# ch455_module.net
KiCad netlist of a schematic drawn in EasyEDA Pro
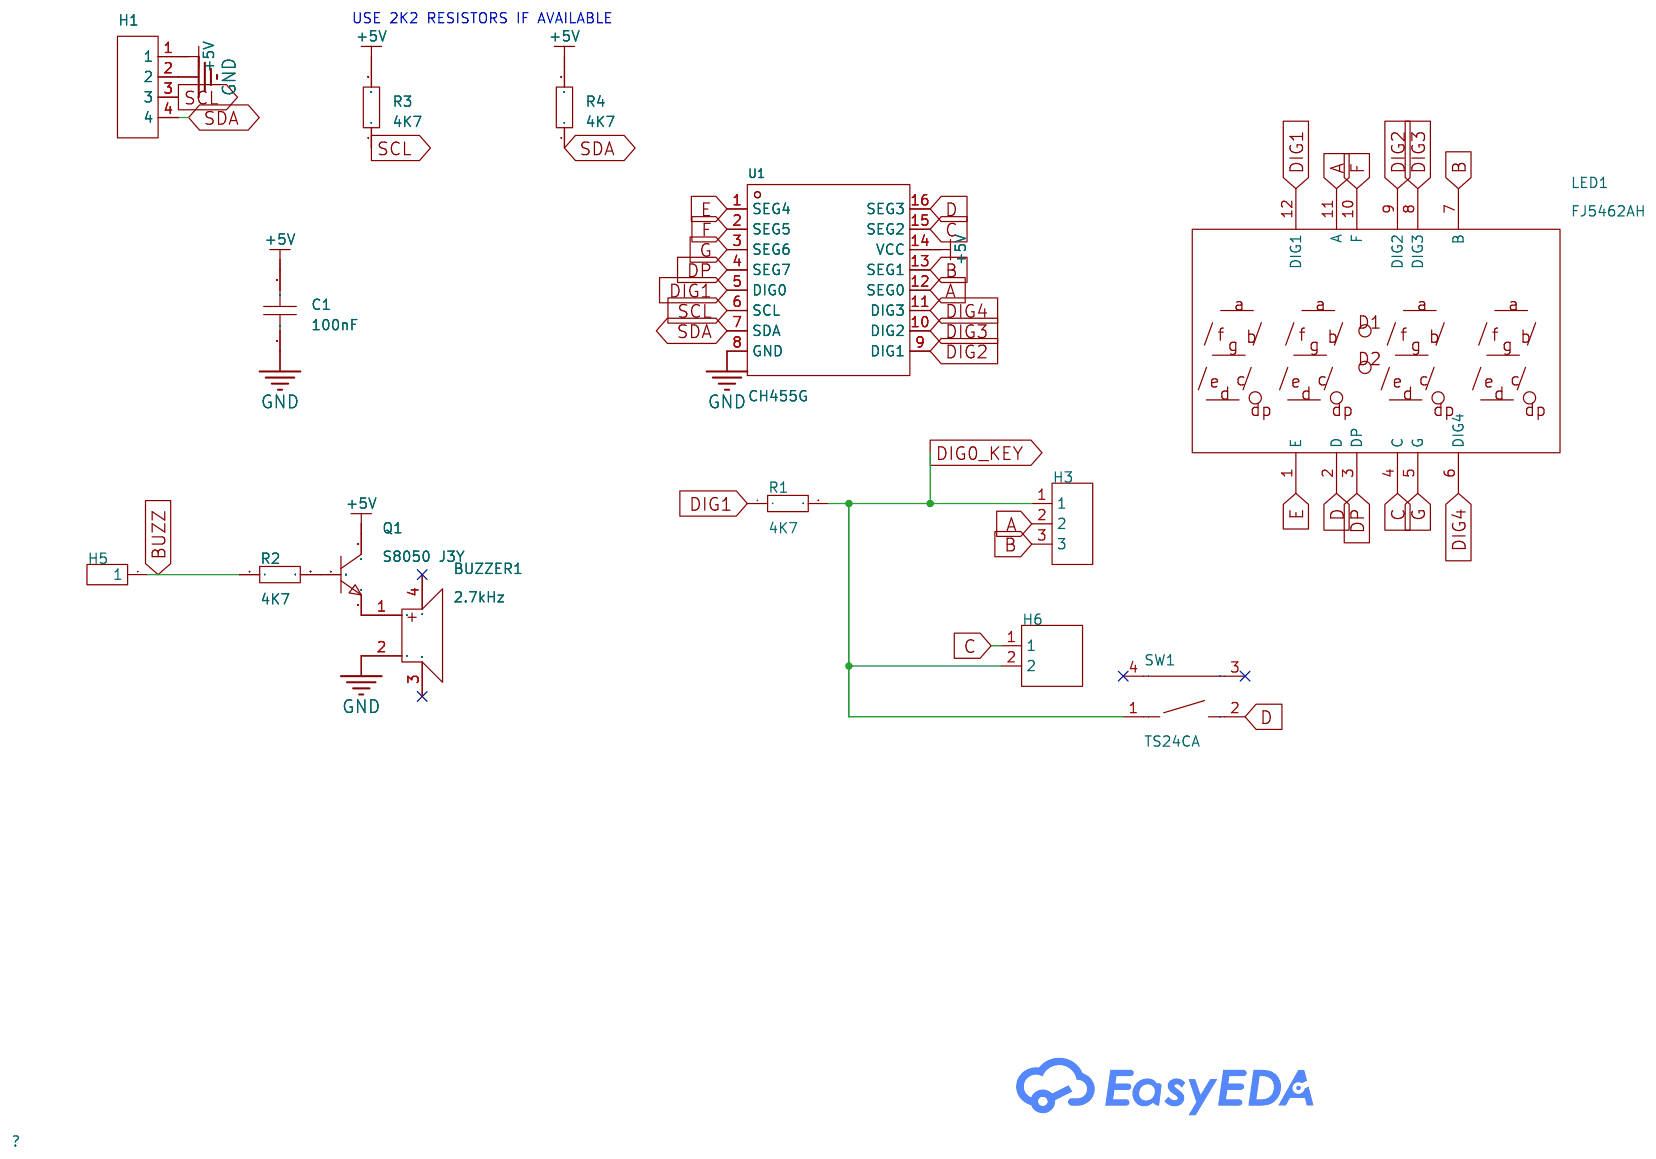
[diagram p0: schematic sheet]

(export (version "E")
  (design (tool "Eeschema 10.0.6"))
  (components
    (comp (ref "BUZZER1")
      (value "2.7kHz")
      (footprint "easyedapro:BUZ-SMD_4P-L8.5-W8.5_FUET-8530-05")
      (fields (field (name "Manufacturer Part") "SMD8530-32Ω") (field (name "Manufacturer") "XHXDZ(兴华鑫)"))
      (libsource (lib "easyedapro") (part "SMD8530-32Ω"))
    )
    (comp (ref "C1")
      (value "100nF")
      (footprint "easyedapro:C0603")
      (libsource (lib "easyedapro") (part "CAP"))
    )
    (comp (ref "H1")
      (value "~")
      (footprint "easyedapro:HDR-TH_4P-P2.54-V-M")
      (libsource (lib "easyedapro") (part "PZ254V-11-04P"))
    )
    (comp (ref "H3")
      (value "~")
      (footprint "easyedapro:HDR-TH_3P-P2.54-V-M")
      (libsource (lib "easyedapro") (part "PZ254V-11-03P_C2937625"))
    )
    (comp (ref "H5")
      (value "~")
      (footprint "easyedapro:HDR-TH_1P-V-M_XKB_X4611WV-01I-C28D40")
      (libsource (lib "easyedapro") (part "HDR_1x1"))
    )
    (comp (ref "H6")
      (value "~")
      (footprint "easyedapro:HDR-TH_2P-P2.54-V-M-1")
      (libsource (lib "easyedapro") (part "210S-1*2P L=11.6MMGold-plated black"))
    )
    (comp (ref "LED1")
      (value "FJ5462AH")
      (footprint "easyedapro:LED-SEG-TH_12P-L50.3-W19.0-P2.54-S15.24-BL")
      (fields (field (name "Manufacturer") "志浩"))
      (libsource (lib "easyedapro") (part "FJ5462AH"))
    )
    (comp (ref "Q1")
      (value "S8050 J3Y")
      (footprint "easyedapro:SOT-23-3_L2.9-W1.3-P0.95-LS2.4-BR")
      (fields (field (name "Manufacturer") "TDSEMIC(拓电半导体)"))
      (libsource (lib "easyedapro") (part "S8050 J3Y_C42441446"))
    )
    (comp (ref "R1") (value "4K7") (footprint "easyedapro:R0603") (libsource (lib "easyedapro") (part "Res")))
    (comp (ref "R2") (value "4K7") (footprint "easyedapro:R0603") (libsource (lib "easyedapro") (part "Res")))
    (comp (ref "R3") (value "4K7") (footprint "easyedapro:R0603") (libsource (lib "easyedapro") (part "Res")))
    (comp (ref "R4") (value "4K7") (footprint "easyedapro:R0603") (libsource (lib "easyedapro") (part "Res")))
    (comp (ref "SW1")
      (value "TS24CA")
      (footprint "easyedapro:SW-SMD_2P-TS24CA")
      (fields (field (name "Manufacturer") "SHOU HAN(首韩)"))
      (libsource (lib "easyedapro") (part "TS24CA"))
    )
    (comp (ref "U1")
      (value "CH455G")
      (footprint "easyedapro:SOP-16_L10.0-W3.9-P1.27-LS6.0-BL")
      (fields (field (name "Manufacturer") "WCH(南京沁恒)"))
      (libsource (lib "easyedapro") (part "CH455G"))
    )
  )
  (nets
    (net (code "1") (name "+5V") (class "Default")
      (node (ref "C1") (pin "1") (pinfunction "1_1") (pintype "input"))
      (node (ref "H1") (pin "1") (pinfunction "1_1") (pintype "unspecified"))
      (node (ref "Q1") (pin "3") (pinfunction "C_3") (pintype "input"))
      (node (ref "R3") (pin "2") (pinfunction "2_2") (pintype "input"))
      (node (ref "R4") (pin "2") (pinfunction "2_2") (pintype "input"))
      (node (ref "U1") (pin "14") (pinfunction "VCC_14") (pintype "input"))
    )
    (net (code "2") (name "A") (class "Default")
      (node (ref "H3") (pin "2") (pinfunction "2_2") (pintype "unspecified"))
      (node (ref "LED1") (pin "11") (pinfunction "A_11") (pintype "input"))
      (node (ref "U1") (pin "12") (pinfunction "SEG0_12") (pintype "input"))
    )
    (net (code "3") (name "B") (class "Default")
      (node (ref "H3") (pin "3") (pinfunction "3_3") (pintype "unspecified"))
      (node (ref "LED1") (pin "7") (pinfunction "B_7") (pintype "input"))
      (node (ref "U1") (pin "13") (pinfunction "SEG1_13") (pintype "input"))
    )
    (net (code "4") (name "BUZZ") (class "Default")
      (node (ref "H5") (pin "1") (pinfunction "1_1") (pintype "unspecified"))
      (node (ref "R2") (pin "1") (pinfunction "1_1") (pintype "input"))
    )
    (net (code "5") (name "C") (class "Default")
      (node (ref "H6") (pin "1") (pinfunction "1_1") (pintype "unspecified"))
      (node (ref "LED1") (pin "4") (pinfunction "C_4") (pintype "input"))
      (node (ref "U1") (pin "15") (pinfunction "SEG2_15") (pintype "input"))
    )
    (net (code "6") (name "D") (class "Default")
      (node (ref "LED1") (pin "2") (pinfunction "D_2") (pintype "input"))
      (node (ref "SW1") (pin "2") (pinfunction "2_2") (pintype "unspecified"))
      (node (ref "U1") (pin "16") (pinfunction "SEG3_16") (pintype "input"))
    )
    (net (code "7") (name "DIG0_KEY") (class "Default")
      (node (ref "H3") (pin "1") (pinfunction "1_1") (pintype "unspecified"))
      (node (ref "H6") (pin "2") (pinfunction "2_2") (pintype "unspecified"))
      (node (ref "R1") (pin "2") (pinfunction "2_2") (pintype "input"))
      (node (ref "SW1") (pin "1") (pinfunction "1_1") (pintype "unspecified"))
    )
    (net (code "8") (name "DIG1") (class "Default")
      (node (ref "LED1") (pin "12") (pinfunction "DIG1_12") (pintype "input"))
      (node (ref "R1") (pin "1") (pinfunction "1_1") (pintype "input"))
      (node (ref "U1") (pin "5") (pinfunction "DIG0_5") (pintype "input"))
    )
    (net (code "9") (name "DIG2") (class "Default")
      (node (ref "LED1") (pin "9") (pinfunction "DIG2_9") (pintype "input"))
      (node (ref "U1") (pin "9") (pinfunction "DIG1_9") (pintype "input"))
    )
    (net (code "10") (name "DIG3") (class "Default")
      (node (ref "LED1") (pin "8") (pinfunction "DIG3_8") (pintype "input"))
      (node (ref "U1") (pin "10") (pinfunction "DIG2_10") (pintype "input"))
    )
    (net (code "11") (name "DIG4") (class "Default")
      (node (ref "LED1") (pin "6") (pinfunction "DIG4_6") (pintype "input"))
      (node (ref "U1") (pin "11") (pinfunction "DIG3_11") (pintype "input"))
    )
    (net (code "12") (name "DP") (class "Default")
      (node (ref "LED1") (pin "3") (pinfunction "DP_3") (pintype "input"))
      (node (ref "U1") (pin "4") (pinfunction "SEG7_4") (pintype "input"))
    )
    (net (code "13") (name "E") (class "Default")
      (node (ref "LED1") (pin "1") (pinfunction "E_1") (pintype "input"))
      (node (ref "U1") (pin "1") (pinfunction "SEG4_1") (pintype "input"))
    )
    (net (code "14") (name "F") (class "Default")
      (node (ref "LED1") (pin "10") (pinfunction "F_10") (pintype "input"))
      (node (ref "U1") (pin "2") (pinfunction "SEG5_2") (pintype "input"))
    )
    (net (code "15") (name "G") (class "Default")
      (node (ref "LED1") (pin "5") (pinfunction "G_5") (pintype "input"))
      (node (ref "U1") (pin "3") (pinfunction "SEG6_3") (pintype "input"))
    )
    (net (code "16") (name "GND") (class "Default")
      (node (ref "BUZZER1") (pin "2") (pinfunction "2_2") (pintype "unspecified"))
      (node (ref "C1") (pin "2") (pinfunction "2_2") (pintype "input"))
      (node (ref "H1") (pin "2") (pinfunction "2_2") (pintype "unspecified"))
      (node (ref "U1") (pin "8") (pinfunction "GND_8") (pintype "input"))
    )
    (net (code "17") (name "Net-(Q1-B)") (class "Default")
      (node (ref "Q1") (pin "1") (pinfunction "B_1") (pintype "input"))
      (node (ref "R2") (pin "2") (pinfunction "2_2") (pintype "input"))
    )
    (net (code "18") (name "Net-(Q1-E)") (class "Default")
      (node (ref "BUZZER1") (pin "1") (pinfunction "1_1") (pintype "unspecified"))
      (node (ref "Q1") (pin "2") (pinfunction "E_2") (pintype "input"))
    )
    (net (code "19") (name "SCL") (class "Default")
      (node (ref "H1") (pin "3") (pinfunction "3_3") (pintype "unspecified"))
      (node (ref "R3") (pin "1") (pinfunction "1_1") (pintype "input"))
      (node (ref "U1") (pin "6") (pinfunction "SCL_6") (pintype "input"))
    )
    (net (code "20") (name "SDA") (class "Default")
      (node (ref "H1") (pin "4") (pinfunction "4_4") (pintype "unspecified"))
      (node (ref "R4") (pin "1") (pinfunction "1_1") (pintype "input"))
      (node (ref "U1") (pin "7") (pinfunction "SDA_7") (pintype "input"))
    )
    (net (code "21") (name "unconnected-(BUZZER1-Pad3)") (class "Default")
      (node (ref "BUZZER1") (pin "3") (pinfunction "3_3") (pintype "unspecified+no_connect"))
    )
    (net (code "22") (name "unconnected-(BUZZER1-Pad4)") (class "Default")
      (node (ref "BUZZER1") (pin "4") (pinfunction "4_4") (pintype "unspecified+no_connect"))
    )
    (net (code "23") (name "unconnected-(SW1-Pad3)") (class "Default")
      (node (ref "SW1") (pin "3") (pinfunction "3_3") (pintype "unspecified+no_connect"))
    )
    (net (code "24") (name "unconnected-(SW1-Pad4)") (class "Default")
      (node (ref "SW1") (pin "4") (pinfunction "4_4") (pintype "unspecified+no_connect"))
    )
  )
)
